# ANALOG.net
KiCad netlist of a schematic drawn in Altium Designer
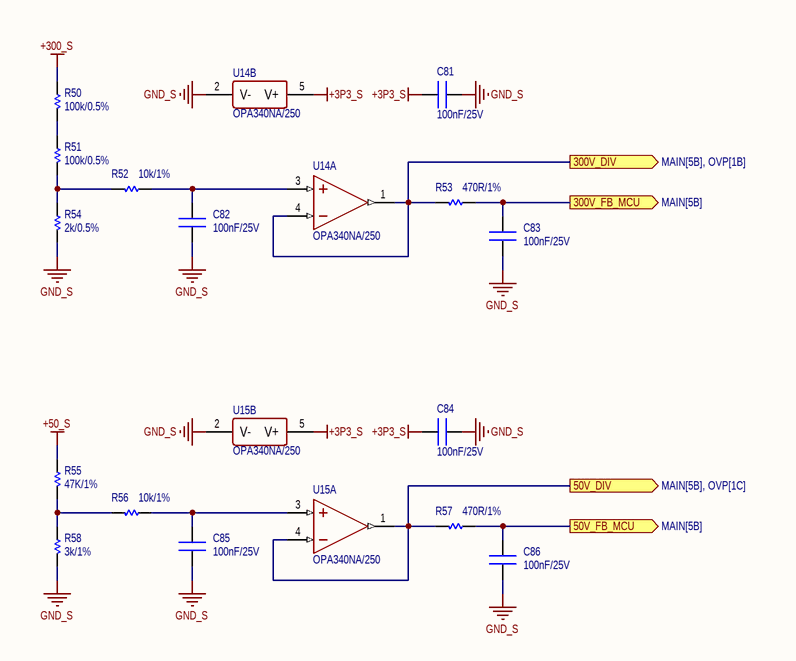
[diagram p0: ANALOG.SchDoc]

(export (version "E")
  (design (tool "Eeschema 10.0.6"))
  (components
    (comp (ref "C81")
      (value "100nF/25V")
      (footprint "CN-SMD-0603")
      (description "CL10B104KA8NNNC")
      (libsource (lib "Library") (part "CN"))
    )
    (comp (ref "C82")
      (value "100nF/25V")
      (footprint "CN-SMD-0603")
      (description "CL10B104KA8NNNC")
      (libsource (lib "Library") (part "CN"))
    )
    (comp (ref "C83")
      (value "100nF/25V")
      (footprint "CN-SMD-0603")
      (description "CL10B104KA8NNNC")
      (libsource (lib "Library") (part "CN"))
    )
    (comp (ref "C84")
      (value "100nF/25V")
      (footprint "CN-SMD-0603")
      (description "CL10B104KA8NNNC")
      (libsource (lib "Library") (part "CN"))
    )
    (comp (ref "C85")
      (value "100nF/25V")
      (footprint "CN-SMD-0603")
      (description "CL10B104KA8NNNC")
      (libsource (lib "Library") (part "CN"))
    )
    (comp (ref "C86")
      (value "100nF/25V")
      (footprint "CN-SMD-0603")
      (description "CL10B104KA8NNNC")
      (libsource (lib "Library") (part "CN"))
    )
    (comp (ref "R50")
      (value "100k/0.5%")
      (footprint "RES-SMD-2010")
      (description "CHV2010-JW-104ELF")
      (fields
        (field (name "MANUFACTURER") "Generic Components")
        (field (name "PUBLISHER") "Altium Hobart Technology Centre")
      )
      (libsource (lib "Library") (part "Res-SMD"))
    )
    (comp (ref "R51")
      (value "100k/0.5%")
      (footprint "RES-SMD-2010")
      (description "CHV2010-JW-104ELF")
      (fields
        (field (name "MANUFACTURER") "Generic Components")
        (field (name "PUBLISHER") "Altium Hobart Technology Centre")
      )
      (libsource (lib "Library") (part "Res-SMD"))
    )
    (comp (ref "R52")
      (value "10k/1%")
      (footprint "RES-SMD-0603")
      (description "ERJ-3EKF1002V")
      (fields
        (field (name "MANUFACTURER") "Generic Components")
        (field (name "PUBLISHER") "Altium Hobart Technology Centre")
      )
      (libsource (lib "Library") (part "Res-SMD"))
    )
    (comp (ref "R53")
      (value "470R/1%")
      (footprint "RES-SMD-0603")
      (description "ERJ-1GJF4700C")
      (fields
        (field (name "MANUFACTURER") "Generic Components")
        (field (name "PUBLISHER") "Altium Hobart Technology Centre")
      )
      (libsource (lib "Library") (part "Res-SMD"))
    )
    (comp (ref "R54")
      (value "2k/0.5%")
      (footprint "RES-SMD-2010")
      (description "CRCW20102K00FKEFHP")
      (fields
        (field (name "MANUFACTURER") "Generic Components")
        (field (name "PUBLISHER") "Altium Hobart Technology Centre")
      )
      (libsource (lib "Library") (part "Res-SMD"))
    )
    (comp (ref "R55")
      (value "47K/1%")
      (footprint "RES-SMD-0603")
      (description "ERJ-3EKF4702V")
      (fields
        (field (name "MANUFACTURER") "Generic Components")
        (field (name "PUBLISHER") "Altium Hobart Technology Centre")
      )
      (libsource (lib "Library") (part "Res-SMD"))
    )
    (comp (ref "R56")
      (value "10k/1%")
      (footprint "RES-SMD-0603")
      (description "ERJ-3EKF1002V")
      (fields
        (field (name "MANUFACTURER") "Generic Components")
        (field (name "PUBLISHER") "Altium Hobart Technology Centre")
      )
      (libsource (lib "Library") (part "Res-SMD"))
    )
    (comp (ref "R57")
      (value "470R/1%")
      (footprint "RES-SMD-0603")
      (description "ERJ-1GJF4700C")
      (fields
        (field (name "MANUFACTURER") "Generic Components")
        (field (name "PUBLISHER") "Altium Hobart Technology Centre")
      )
      (libsource (lib "Library") (part "Res-SMD"))
    )
    (comp (ref "R58")
      (value "3k/1%")
      (footprint "RES-SMD-0603")
      (description "ERA-3AEB302V")
      (fields
        (field (name "MANUFACTURER") "Generic Components")
        (field (name "PUBLISHER") "Altium Hobart Technology Centre")
      )
      (libsource (lib "Library") (part "Res-SMD"))
    )
    (comp (ref "U14")
      (value "OPA340NA/250")
      (footprint "SOT23-5")
      (libsource (lib "Library") (part "OPA340DBV"))
    )
    (comp (ref "U15")
      (value "OPA340NA/250")
      (footprint "SOT23-5")
      (libsource (lib "Library") (part "OPA340DBV"))
    )
  )
  (nets
    (net (code "1") (name "+3P3_S") (class "Default")
      (node (ref "C81") (pin "1") (pinfunction "1_1") (pintype "passive"))
      (node (ref "C84") (pin "1") (pinfunction "1_1") (pintype "passive"))
      (node (ref "U14") (pin "5") (pinfunction "V+_5") (pintype "passive"))
      (node (ref "U15") (pin "5") (pinfunction "V+_5") (pintype "passive"))
    )
    (net (code "2") (name "+50_S") (class "Default")
      (node (ref "R55") (pin "1") (pinfunction "1_1") (pintype "passive"))
    )
    (net (code "3") (name "+300_S") (class "Default")
      (node (ref "R50") (pin "1") (pinfunction "1_1") (pintype "passive"))
    )
    (net (code "4") (name "/50V_DIV") (class "Default")
      (node (ref "R57") (pin "2") (pinfunction "2_2") (pintype "passive"))
      (node (ref "U15") (pin "1") (pinfunction "OUT_1") (pintype "output"))
      (node (ref "U15") (pin "4") (pinfunction "IN-_4") (pintype "input"))
    )
    (net (code "5") (name "/50V_FB_MCU") (class "Default")
      (node (ref "C86") (pin "1") (pinfunction "1_1") (pintype "passive"))
      (node (ref "R57") (pin "1") (pinfunction "1_1") (pintype "passive"))
    )
    (net (code "6") (name "/300V_DIV") (class "Default")
      (node (ref "R53") (pin "2") (pinfunction "2_2") (pintype "passive"))
      (node (ref "U14") (pin "1") (pinfunction "OUT_1") (pintype "output"))
      (node (ref "U14") (pin "4") (pinfunction "IN-_4") (pintype "input"))
    )
    (net (code "7") (name "/300V_FB_MCU") (class "Default")
      (node (ref "C83") (pin "1") (pinfunction "1_1") (pintype "passive"))
      (node (ref "R53") (pin "1") (pinfunction "1_1") (pintype "passive"))
    )
    (net (code "8") (name "GND_S") (class "Default")
      (node (ref "C81") (pin "2") (pinfunction "2_2") (pintype "passive"))
      (node (ref "C82") (pin "2") (pinfunction "2_2") (pintype "passive"))
      (node (ref "C83") (pin "2") (pinfunction "2_2") (pintype "passive"))
      (node (ref "C84") (pin "2") (pinfunction "2_2") (pintype "passive"))
      (node (ref "C85") (pin "2") (pinfunction "2_2") (pintype "passive"))
      (node (ref "C86") (pin "2") (pinfunction "2_2") (pintype "passive"))
      (node (ref "R54") (pin "2") (pinfunction "2_2") (pintype "passive"))
      (node (ref "R58") (pin "2") (pinfunction "2_2") (pintype "passive"))
      (node (ref "U14") (pin "2") (pinfunction "V-_2") (pintype "passive"))
      (node (ref "U15") (pin "2") (pinfunction "V-_2") (pintype "passive"))
    )
    (net (code "9") (name "Net-(R50-Pad2)") (class "Default")
      (node (ref "R50") (pin "2") (pinfunction "2_2") (pintype "passive"))
      (node (ref "R51") (pin "1") (pinfunction "1_1") (pintype "passive"))
    )
    (net (code "10") (name "Net-(R51-Pad2)") (class "Default")
      (node (ref "R51") (pin "2") (pinfunction "2_2") (pintype "passive"))
      (node (ref "R52") (pin "2") (pinfunction "2_2") (pintype "passive"))
      (node (ref "R54") (pin "1") (pinfunction "1_1") (pintype "passive"))
    )
    (net (code "11") (name "Net-(R55-Pad2)") (class "Default")
      (node (ref "R55") (pin "2") (pinfunction "2_2") (pintype "passive"))
      (node (ref "R56") (pin "2") (pinfunction "2_2") (pintype "passive"))
      (node (ref "R58") (pin "1") (pinfunction "1_1") (pintype "passive"))
    )
    (net (code "12") (name "Net-(U14A-IN+)") (class "Default")
      (node (ref "C82") (pin "1") (pinfunction "1_1") (pintype "passive"))
      (node (ref "R52") (pin "1") (pinfunction "1_1") (pintype "passive"))
      (node (ref "U14") (pin "3") (pinfunction "IN+_3") (pintype "input"))
    )
    (net (code "13") (name "Net-(U15A-IN+)") (class "Default")
      (node (ref "C85") (pin "1") (pinfunction "1_1") (pintype "passive"))
      (node (ref "R56") (pin "1") (pinfunction "1_1") (pintype "passive"))
      (node (ref "U15") (pin "3") (pinfunction "IN+_3") (pintype "input"))
    )
  )
)
